# stc15.net
KiCad netlist of a schematic drawn in Altium Designer
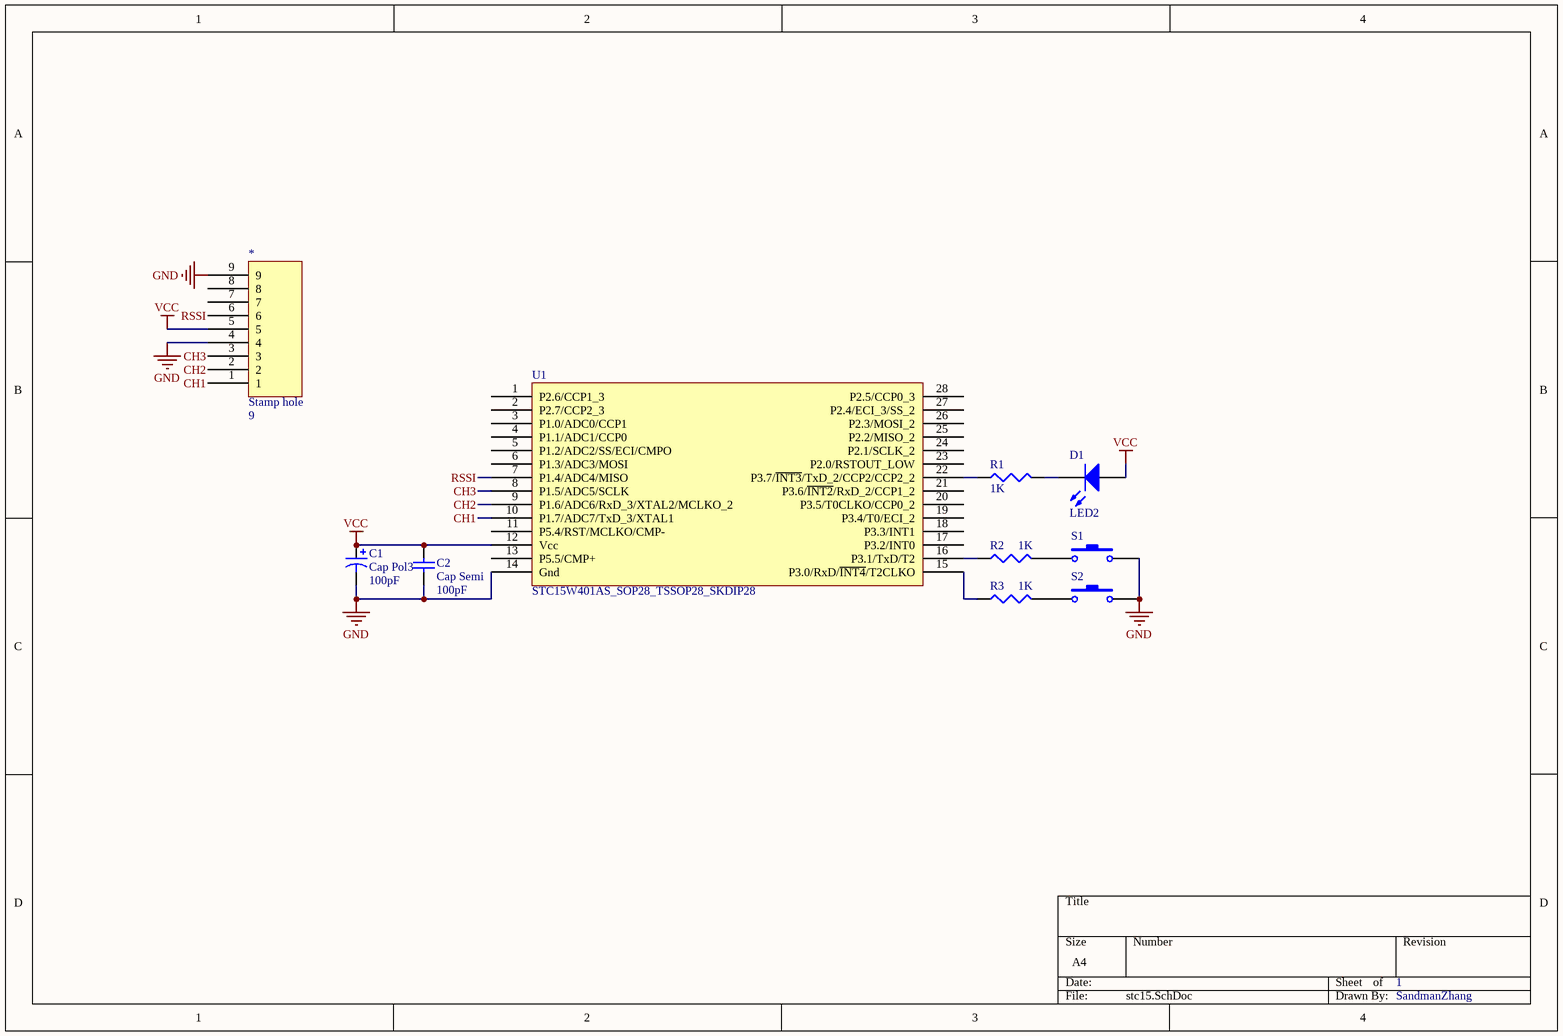
[diagram p0: stc15.SchDoc]

(export (version "E")
  (design (tool "Eeschema 10.0.6"))
  (components
    (comp (ref "*") (value "9") (footprint "9") (libsource (lib "stamphole") (part "9")))
    (comp (ref "C1")
      (value "Cap Pol3")
      (footprint "C0805")
      (description "Polarized Capacitor (Surface Mount)")
      (fields (field (name "ALTIUM_VALUE") "100pF") (field (name "PUBLISHER") "Altium Limited"))
      (libsource (lib "Miscellaneous Devices") (part "Cap Pol3"))
    )
    (comp (ref "C2")
      (value "Cap Semi")
      (footprint "1608[0603]")
      (description "Capacitor (Semiconductor SIM Model)")
      (fields (field (name "ALTIUM_VALUE") "100pF") (field (name "PUBLISHER") "Altium Limited"))
      (libsource (lib "Miscellaneous Devices") (part "Cap Semi"))
    )
    (comp (ref "D1")
      (value "LED2")
      (footprint "Miscellaneous Devices:6-0805_N")
      (description "Typical RED, GREEN, YELLOW, AMBER GaAs LED")
      (fields (field (name "PUBLISHER") "Altium Limited"))
      (libsource (lib "Miscellaneous Devices") (part "LED2"))
    )
    (comp (ref "R1")
      (value "1K")
      (footprint "J1-0603")
      (description "Resistor")
      (fields (field (name "Comment") "Res3") (field (name "PUBLISHER") "Altium Limited"))
      (libsource (lib "Miscellaneous Devices") (part "Res3"))
    )
    (comp (ref "R2")
      (value "1K")
      (footprint "J1-0603")
      (description "Resistor")
      (fields (field (name "Comment") "Res3") (field (name "PUBLISHER") "Altium Limited"))
      (libsource (lib "Miscellaneous Devices") (part "Res3"))
    )
    (comp (ref "R3")
      (value "1K")
      (footprint "J1-0603")
      (description "Resistor")
      (fields (field (name "Comment") "Res3") (field (name "PUBLISHER") "Altium Limited"))
      (libsource (lib "Miscellaneous Devices") (part "Res3"))
    )
    (comp (ref "S1")
      (value "SW-PB")
      (footprint "SPST-2")
      (description "Switch")
      (fields (field (name "PUBLISHER") "Altium Limited"))
      (libsource (lib "Miscellaneous Devices") (part "SW-PB"))
    )
    (comp (ref "S2")
      (value "SW-PB")
      (footprint "SPST-2")
      (description "Switch")
      (fields (field (name "PUBLISHER") "Altium Limited"))
      (libsource (lib "Miscellaneous Devices") (part "SW-PB"))
    )
    (comp (ref "U1")
      (value "STC15W401AS_SOP28_TSSOP28_SKDIP28")
      (footprint "SOP28")
      (libsource (lib "stcmcu_altium20.1.10") (part "STC15W401AS_SOP28_TSSOP28_SKDIP28"))
    )
  )
  (nets
    (net (code "1") (name "/CH1") (class "Default")
      (node (ref "*") (pin "1") (pinfunction "1_1") (pintype "passive"))
      (node (ref "U1") (pin "10") (pinfunction "P1.7/ADC7/TxD_3/XTAL1_10") (pintype "passive"))
    )
    (net (code "2") (name "/CH2") (class "Default")
      (node (ref "*") (pin "2") (pinfunction "2_2") (pintype "passive"))
      (node (ref "U1") (pin "9") (pinfunction "P1.6/ADC6/RxD_3/XTAL2/MCLKO_2_9") (pintype "passive"))
    )
    (net (code "3") (name "/CH3") (class "Default")
      (node (ref "*") (pin "3") (pinfunction "3_3") (pintype "passive"))
      (node (ref "U1") (pin "8") (pinfunction "P1.5/ADC5/SCLK_8") (pintype "passive"))
    )
    (net (code "4") (name "/RSSI") (class "Default")
      (node (ref "*") (pin "6") (pinfunction "6_6") (pintype "passive"))
      (node (ref "U1") (pin "7") (pinfunction "P1.4/ADC4/MISO_7") (pintype "passive"))
    )
    (net (code "5") (name "GND") (class "Default")
      (node (ref "*") (pin "4") (pinfunction "4_4") (pintype "passive"))
      (node (ref "*") (pin "9") (pinfunction "9_9") (pintype "passive"))
      (node (ref "C1") (pin "2") (pinfunction "2_2") (pintype "passive"))
      (node (ref "C2") (pin "1") (pinfunction "1_1") (pintype "passive"))
      (node (ref "S1") (pin "2") (pinfunction "2_2") (pintype "passive"))
      (node (ref "S2") (pin "2") (pinfunction "2_2") (pintype "passive"))
      (node (ref "U1") (pin "14") (pinfunction "Gnd_14") (pintype "passive"))
    )
    (net (code "6") (name "Net-(D1-K)") (class "Default")
      (node (ref "D1") (pin "2") (pinfunction "K_2") (pintype "passive"))
      (node (ref "R1") (pin "2") (pinfunction "2_2") (pintype "passive"))
    )
    (net (code "7") (name "Net-(R2-Pad2)") (class "Default")
      (node (ref "R2") (pin "2") (pinfunction "2_2") (pintype "passive"))
      (node (ref "S1") (pin "1") (pinfunction "1_1") (pintype "passive"))
    )
    (net (code "8") (name "Net-(R3-Pad2)") (class "Default")
      (node (ref "R3") (pin "2") (pinfunction "2_2") (pintype "passive"))
      (node (ref "S2") (pin "1") (pinfunction "1_1") (pintype "passive"))
    )
    (net (code "9") (name "Net-(U1-P3.0{slash}RxD{slash}~{INT4}{slash}T2CLKO)") (class "Default")
      (node (ref "R3") (pin "1") (pinfunction "1_1") (pintype "passive"))
      (node (ref "U1") (pin "15") (pinfunction "P3.0/RxD/~{INT4}/T2CLKO_15") (pintype "passive"))
    )
    (net (code "10") (name "Net-(U1-P3.1{slash}TxD{slash}T2)") (class "Default")
      (node (ref "R2") (pin "1") (pinfunction "1_1") (pintype "passive"))
      (node (ref "U1") (pin "16") (pinfunction "P3.1/TxD/T2_16") (pintype "passive"))
    )
    (net (code "11") (name "Net-(U1-P3.7{slash}~{INT3}{slash}TxD_2{slash}CCP2{slash}CCP2_2)") (class "Default")
      (node (ref "R1") (pin "1") (pinfunction "1_1") (pintype "passive"))
      (node (ref "U1") (pin "22") (pinfunction "P3.7/~{INT3}/TxD_2/CCP2/CCP2_2_22") (pintype "passive"))
    )
    (net (code "12") (name "VCC") (class "Default")
      (node (ref "*") (pin "5") (pinfunction "5_5") (pintype "passive"))
      (node (ref "C1") (pin "1") (pinfunction "1_1") (pintype "passive"))
      (node (ref "C2") (pin "2") (pinfunction "2_2") (pintype "passive"))
      (node (ref "D1") (pin "1") (pinfunction "A_1") (pintype "passive"))
      (node (ref "U1") (pin "12") (pinfunction "Vcc_12") (pintype "passive"))
    )
    (net (code "13") (name "unconnected-(*-Pad7)") (class "Default")
      (node (ref "*") (pin "7") (pinfunction "7_7") (pintype "passive"))
    )
    (net (code "14") (name "unconnected-(*-Pad8)") (class "Default")
      (node (ref "*") (pin "8") (pinfunction "8_8") (pintype "passive"))
    )
    (net (code "15") (name "unconnected-(U1-P1.0{slash}ADC0{slash}CCP1-Pad3)") (class "Default")
      (node (ref "U1") (pin "3") (pinfunction "P1.0/ADC0/CCP1_3") (pintype "passive"))
    )
    (net (code "16") (name "unconnected-(U1-P1.1{slash}ADC1{slash}CCP0-Pad4)") (class "Default")
      (node (ref "U1") (pin "4") (pinfunction "P1.1/ADC1/CCP0_4") (pintype "passive"))
    )
    (net (code "17") (name "unconnected-(U1-P1.2{slash}ADC2{slash}SS{slash}ECI{slash}CMPO-Pad5)") (class "Default")
      (node (ref "U1") (pin "5") (pinfunction "P1.2/ADC2/SS/ECI/CMPO_5") (pintype "passive"))
    )
    (net (code "18") (name "unconnected-(U1-P1.3{slash}ADC3{slash}MOSI-Pad6)") (class "Default")
      (node (ref "U1") (pin "6") (pinfunction "P1.3/ADC3/MOSI_6") (pintype "passive"))
    )
    (net (code "19") (name "unconnected-(U1-P2.0{slash}RSTOUT_LOW-Pad23)") (class "Default")
      (node (ref "U1") (pin "23") (pinfunction "P2.0/RSTOUT_LOW_23") (pintype "passive"))
    )
    (net (code "20") (name "unconnected-(U1-P2.1{slash}SCLK_2-Pad24)") (class "Default")
      (node (ref "U1") (pin "24") (pinfunction "P2.1/SCLK_2_24") (pintype "passive"))
    )
    (net (code "21") (name "unconnected-(U1-P2.2{slash}MISO_2-Pad25)") (class "Default")
      (node (ref "U1") (pin "25") (pinfunction "P2.2/MISO_2_25") (pintype "passive"))
    )
    (net (code "22") (name "unconnected-(U1-P2.3{slash}MOSI_2-Pad26)") (class "Default")
      (node (ref "U1") (pin "26") (pinfunction "P2.3/MOSI_2_26") (pintype "passive"))
    )
    (net (code "23") (name "unconnected-(U1-P2.4{slash}ECI_3{slash}SS_2-Pad27)") (class "Default")
      (node (ref "U1") (pin "27") (pinfunction "P2.4/ECI_3/SS_2_27") (pintype "passive"))
    )
    (net (code "24") (name "unconnected-(U1-P2.5{slash}CCP0_3-Pad28)") (class "Default")
      (node (ref "U1") (pin "28") (pinfunction "P2.5/CCP0_3_28") (pintype "passive"))
    )
    (net (code "25") (name "unconnected-(U1-P2.6{slash}CCP1_3-Pad1)") (class "Default")
      (node (ref "U1") (pin "1") (pinfunction "P2.6/CCP1_3_1") (pintype "passive"))
    )
    (net (code "26") (name "unconnected-(U1-P2.7{slash}CCP2_3-Pad2)") (class "Default")
      (node (ref "U1") (pin "2") (pinfunction "P2.7/CCP2_3_2") (pintype "passive"))
    )
    (net (code "27") (name "unconnected-(U1-P3.2{slash}INT0-Pad17)") (class "Default")
      (node (ref "U1") (pin "17") (pinfunction "P3.2/INT0_17") (pintype "passive"))
    )
    (net (code "28") (name "unconnected-(U1-P3.3{slash}INT1-Pad18)") (class "Default")
      (node (ref "U1") (pin "18") (pinfunction "P3.3/INT1_18") (pintype "passive"))
    )
    (net (code "29") (name "unconnected-(U1-P3.4{slash}T0{slash}ECI_2-Pad19)") (class "Default")
      (node (ref "U1") (pin "19") (pinfunction "P3.4/T0/ECI_2_19") (pintype "passive"))
    )
    (net (code "30") (name "unconnected-(U1-P3.5{slash}T0CLKO{slash}CCP0_2-Pad20)") (class "Default")
      (node (ref "U1") (pin "20") (pinfunction "P3.5/T0CLKO/CCP0_2_20") (pintype "passive"))
    )
    (net (code "31") (name "unconnected-(U1-P3.6{slash}~{INT2}{slash}RxD_2{slash}CCP1_2-Pad21)") (class "Default")
      (node (ref "U1") (pin "21") (pinfunction "P3.6/~{INT2}/RxD_2/CCP1_2_21") (pintype "passive"))
    )
    (net (code "32") (name "unconnected-(U1-P5.4{slash}RST{slash}MCLKO{slash}CMP--Pad11)") (class "Default")
      (node (ref "U1") (pin "11") (pinfunction "P5.4/RST/MCLKO/CMP-_11") (pintype "passive"))
    )
    (net (code "33") (name "unconnected-(U1-P5.5{slash}CMP+-Pad13)") (class "Default")
      (node (ref "U1") (pin "13") (pinfunction "P5.5/CMP+_13") (pintype "passive"))
    )
  )
)
